# Robot_schematic.net
KiCad netlist of a schematic drawn in EasyEDA
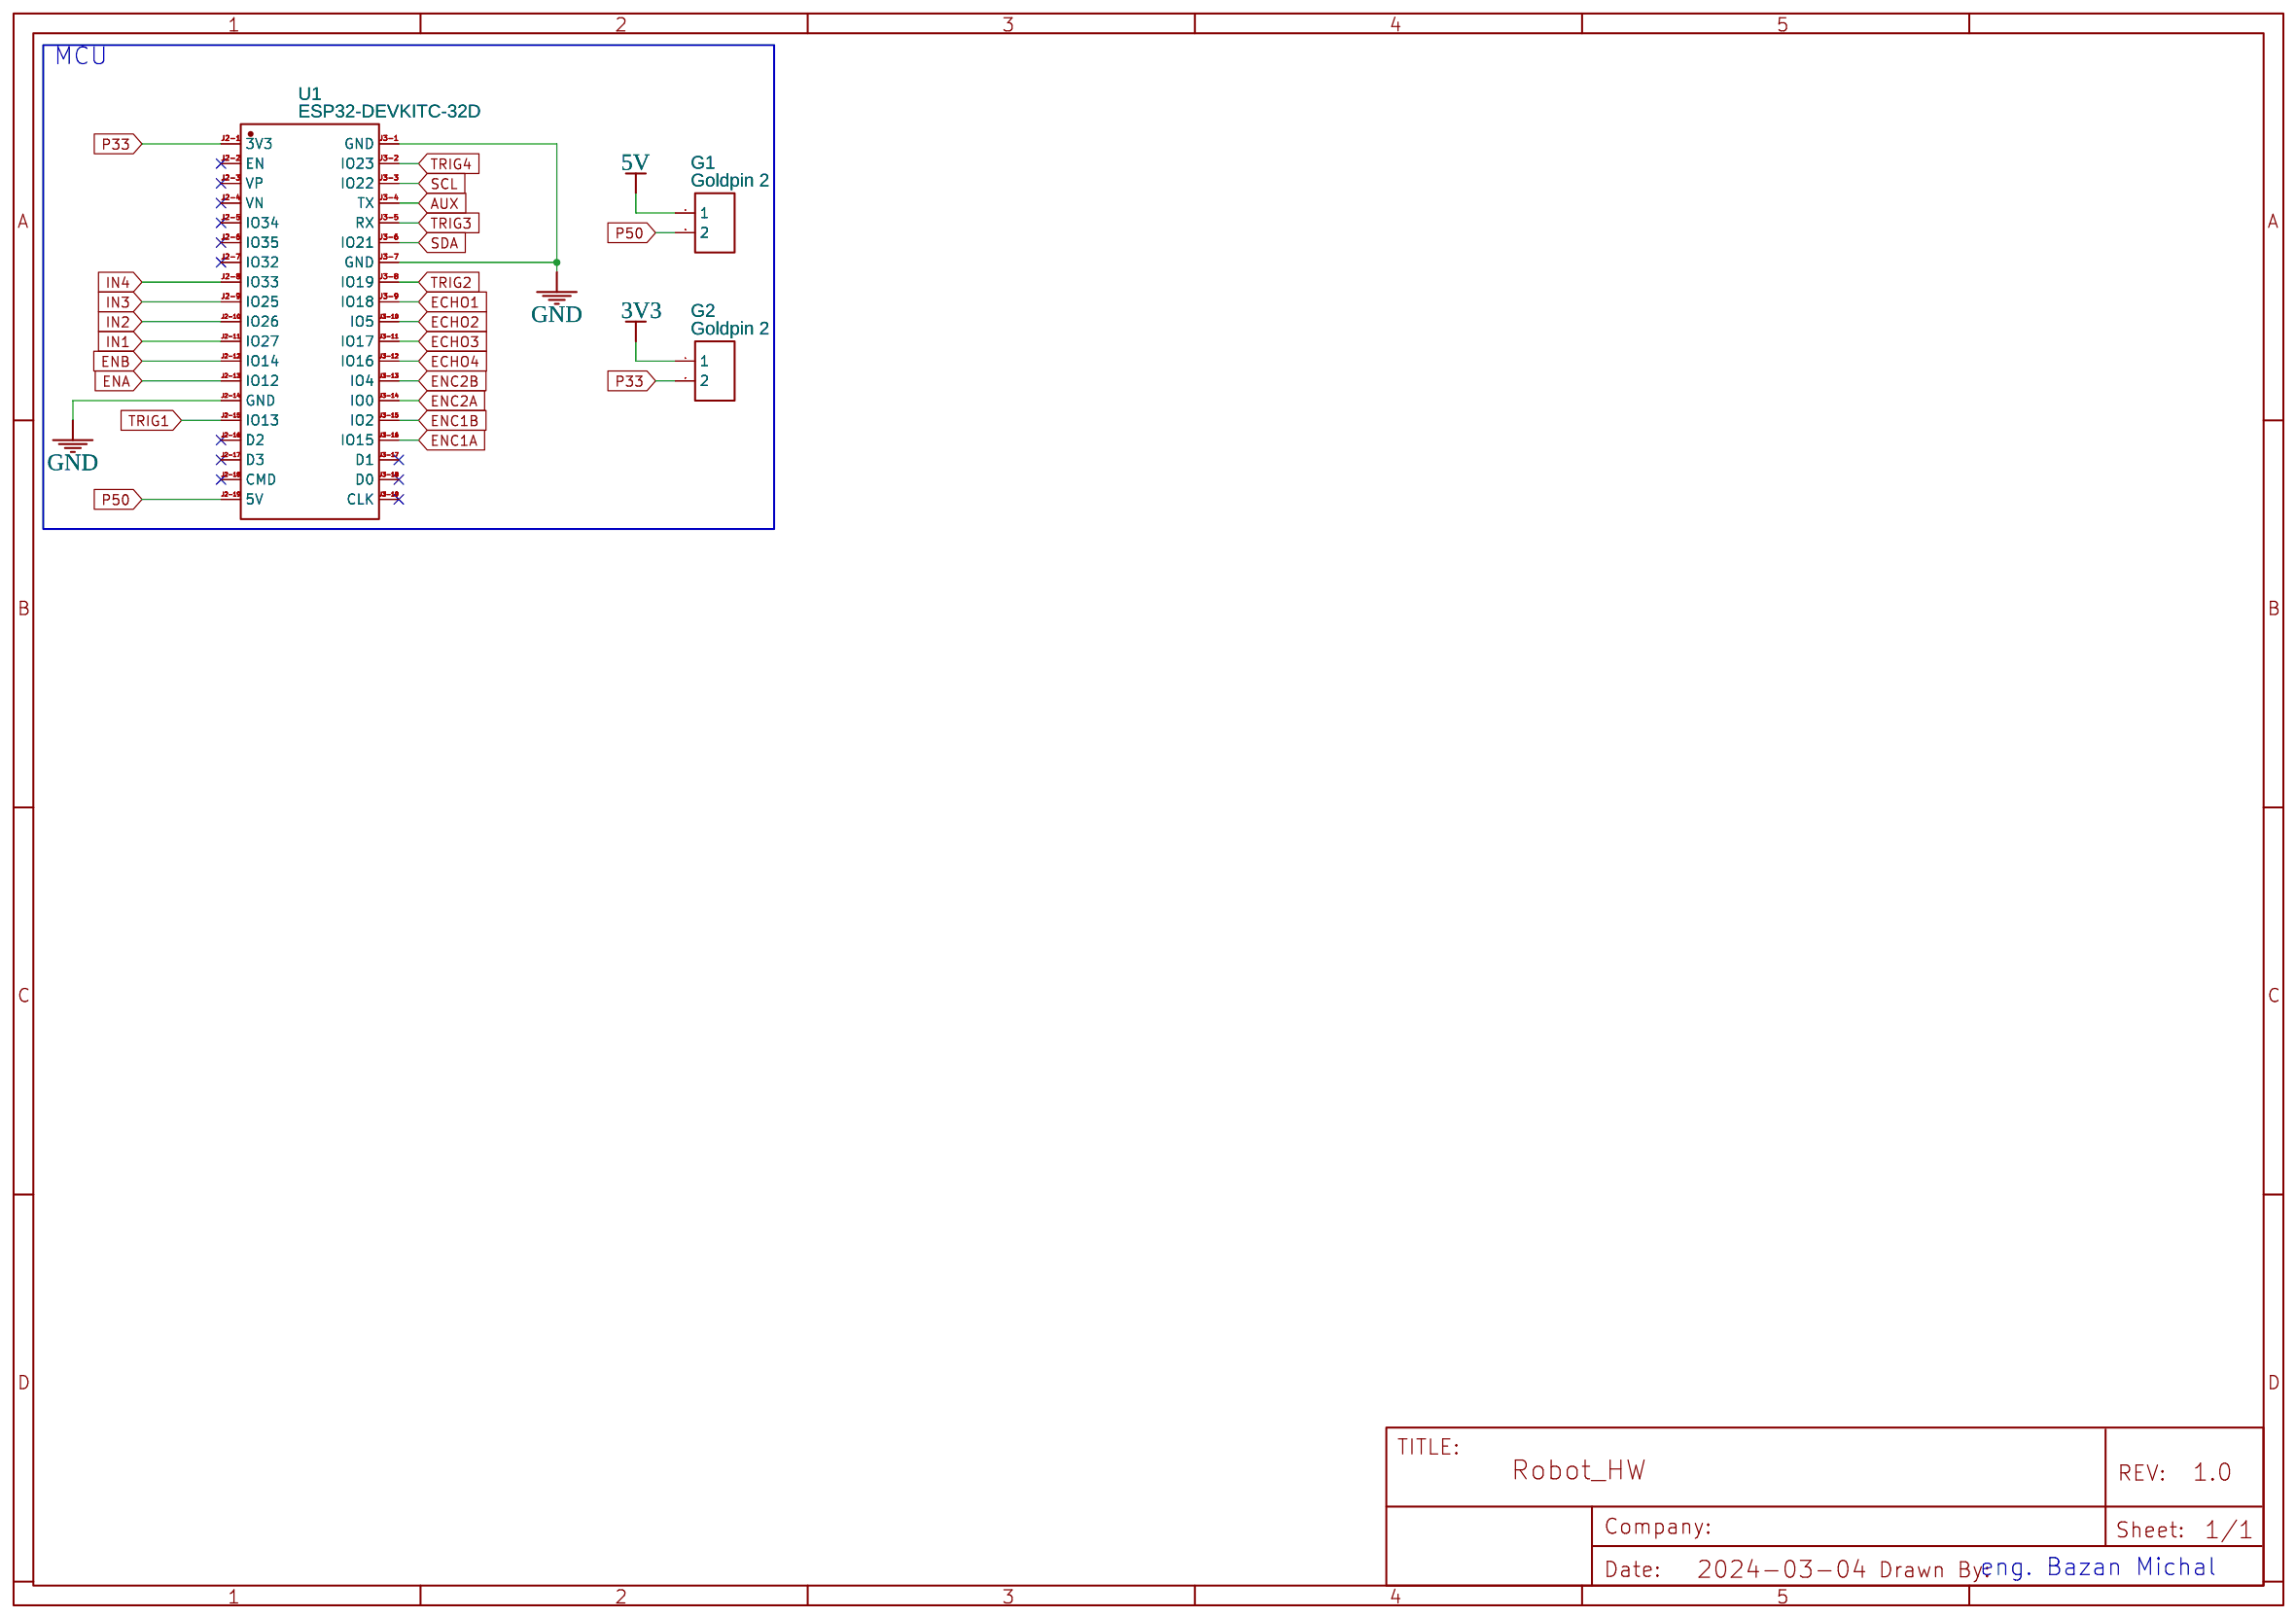
[diagram p0: schematic sheet]

(export (version "E")
  (design (tool "Eeschema 10.0.6"))
  (components
    (comp (ref "G1") (value "Goldpin 2") (libsource (lib "") (part "Goldpin 2")))
    (comp (ref "G2") (value "Goldpin 2") (libsource (lib "") (part "Goldpin 2")))
    (comp (ref "U1")
      (value "ESP32-DEVKITC-32D")
      (fields
        (field (name "Manufacturer Part") "ESP32-DevKitC-32D")
        (field (name "Manufacturer") "ESPRESSIF(乐鑫)")
      )
      (libsource (lib "") (part "ESP32-DEVKITC-32D"))
    )
  )
  (nets
    (net (code "1") (name "3V3") (class "Default")
      (node (ref "G2") (pin "1") (pinfunction "1_1") (pintype "input"))
    )
    (net (code "2") (name "5V") (class "Default")
      (node (ref "G1") (pin "1") (pinfunction "1_1") (pintype "input"))
    )
    (net (code "3") (name "AUX") (class "Default")
      (node (ref "U1") (pin "J3-4") (pinfunction "TX_J3-4") (pintype "unspecified"))
    )
    (net (code "4") (name "ECHO1") (class "Default")
      (node (ref "U1") (pin "J3-9") (pinfunction "IO18_J3-9") (pintype "unspecified"))
    )
    (net (code "5") (name "ECHO2") (class "Default")
      (node (ref "U1") (pin "J3-10") (pinfunction "IO5_J3-10") (pintype "unspecified"))
    )
    (net (code "6") (name "ECHO3") (class "Default")
      (node (ref "U1") (pin "J3-11") (pinfunction "IO17_J3-11") (pintype "unspecified"))
    )
    (net (code "7") (name "ECHO4") (class "Default")
      (node (ref "U1") (pin "J3-12") (pinfunction "IO16_J3-12") (pintype "unspecified"))
    )
    (net (code "8") (name "ENA") (class "Default")
      (node (ref "U1") (pin "J2-13") (pinfunction "IO12_J2-13") (pintype "unspecified"))
    )
    (net (code "9") (name "ENB") (class "Default")
      (node (ref "U1") (pin "J2-12") (pinfunction "IO14_J2-12") (pintype "unspecified"))
    )
    (net (code "10") (name "ENC1A") (class "Default")
      (node (ref "U1") (pin "J3-16") (pinfunction "IO15_J3-16") (pintype "unspecified"))
    )
    (net (code "11") (name "ENC1B") (class "Default")
      (node (ref "U1") (pin "J3-15") (pinfunction "IO2_J3-15") (pintype "unspecified"))
    )
    (net (code "12") (name "ENC2A") (class "Default")
      (node (ref "U1") (pin "J3-14") (pinfunction "IO0_J3-14") (pintype "unspecified"))
    )
    (net (code "13") (name "ENC2B") (class "Default")
      (node (ref "U1") (pin "J3-13") (pinfunction "IO4_J3-13") (pintype "unspecified"))
    )
    (net (code "14") (name "GND") (class "Default")
      (node (ref "U1") (pin "J2-14") (pinfunction "GND_J2-14") (pintype "unspecified"))
      (node (ref "U1") (pin "J3-1") (pinfunction "GND_J3-1") (pintype "unspecified"))
      (node (ref "U1") (pin "J3-7") (pinfunction "GND_J3-7") (pintype "unspecified"))
    )
    (net (code "15") (name "IN1") (class "Default")
      (node (ref "U1") (pin "J2-11") (pinfunction "IO27_J2-11") (pintype "unspecified"))
    )
    (net (code "16") (name "IN2") (class "Default")
      (node (ref "U1") (pin "J2-10") (pinfunction "IO26_J2-10") (pintype "unspecified"))
    )
    (net (code "17") (name "IN3") (class "Default")
      (node (ref "U1") (pin "J2-9") (pinfunction "IO25_J2-9") (pintype "unspecified"))
    )
    (net (code "18") (name "IN4") (class "Default")
      (node (ref "U1") (pin "J2-8") (pinfunction "IO33_J2-8") (pintype "unspecified"))
    )
    (net (code "19") (name "P33") (class "Default")
      (node (ref "G2") (pin "2") (pinfunction "2_2") (pintype "input"))
      (node (ref "U1") (pin "J2-1") (pinfunction "3V3_J2-1") (pintype "unspecified"))
    )
    (net (code "20") (name "P50") (class "Default")
      (node (ref "G1") (pin "2") (pinfunction "2_2") (pintype "input"))
      (node (ref "U1") (pin "J2-19") (pinfunction "5V_J2-19") (pintype "unspecified"))
    )
    (net (code "21") (name "SCL") (class "Default")
      (node (ref "U1") (pin "J3-3") (pinfunction "IO22_J3-3") (pintype "unspecified"))
    )
    (net (code "22") (name "SDA") (class "Default")
      (node (ref "U1") (pin "J3-6") (pinfunction "IO21_J3-6") (pintype "unspecified"))
    )
    (net (code "23") (name "TRIG1") (class "Default")
      (node (ref "U1") (pin "J2-15") (pinfunction "IO13_J2-15") (pintype "unspecified"))
    )
    (net (code "24") (name "TRIG2") (class "Default")
      (node (ref "U1") (pin "J3-8") (pinfunction "IO19_J3-8") (pintype "unspecified"))
    )
    (net (code "25") (name "TRIG3") (class "Default")
      (node (ref "U1") (pin "J3-5") (pinfunction "RX_J3-5") (pintype "unspecified"))
    )
    (net (code "26") (name "TRIG4") (class "Default")
      (node (ref "U1") (pin "J3-2") (pinfunction "IO23_J3-2") (pintype "unspecified"))
    )
    (net (code "27") (name "unconnected-(U1-CLK-PadJ3-19)") (class "Default")
      (node (ref "U1") (pin "J3-19") (pinfunction "CLK_J3-19") (pintype "unspecified+no_connect"))
    )
    (net (code "28") (name "unconnected-(U1-CMD-PadJ2-18)") (class "Default")
      (node (ref "U1") (pin "J2-18") (pinfunction "CMD_J2-18") (pintype "unspecified+no_connect"))
    )
    (net (code "29") (name "unconnected-(U1-D0-PadJ3-18)") (class "Default")
      (node (ref "U1") (pin "J3-18") (pinfunction "D0_J3-18") (pintype "unspecified+no_connect"))
    )
    (net (code "30") (name "unconnected-(U1-D1-PadJ3-17)") (class "Default")
      (node (ref "U1") (pin "J3-17") (pinfunction "D1_J3-17") (pintype "unspecified+no_connect"))
    )
    (net (code "31") (name "unconnected-(U1-D2-PadJ2-16)") (class "Default")
      (node (ref "U1") (pin "J2-16") (pinfunction "D2_J2-16") (pintype "unspecified+no_connect"))
    )
    (net (code "32") (name "unconnected-(U1-D3-PadJ2-17)") (class "Default")
      (node (ref "U1") (pin "J2-17") (pinfunction "D3_J2-17") (pintype "unspecified+no_connect"))
    )
    (net (code "33") (name "unconnected-(U1-EN-PadJ2-2)") (class "Default")
      (node (ref "U1") (pin "J2-2") (pinfunction "EN_J2-2") (pintype "unspecified+no_connect"))
    )
    (net (code "34") (name "unconnected-(U1-IO32-PadJ2-7)") (class "Default")
      (node (ref "U1") (pin "J2-7") (pinfunction "IO32_J2-7") (pintype "unspecified+no_connect"))
    )
    (net (code "35") (name "unconnected-(U1-IO34-PadJ2-5)") (class "Default")
      (node (ref "U1") (pin "J2-5") (pinfunction "IO34_J2-5") (pintype "unspecified+no_connect"))
    )
    (net (code "36") (name "unconnected-(U1-IO35-PadJ2-6)") (class "Default")
      (node (ref "U1") (pin "J2-6") (pinfunction "IO35_J2-6") (pintype "unspecified+no_connect"))
    )
    (net (code "37") (name "unconnected-(U1-VN-PadJ2-4)") (class "Default")
      (node (ref "U1") (pin "J2-4") (pinfunction "VN_J2-4") (pintype "unspecified+no_connect"))
    )
    (net (code "38") (name "unconnected-(U1-VP-PadJ2-3)") (class "Default")
      (node (ref "U1") (pin "J2-3") (pinfunction "VP_J2-3") (pintype "unspecified+no_connect"))
    )
  )
)
